# Power_ESP32.net
KiCad netlist of a schematic drawn in Altium Designer
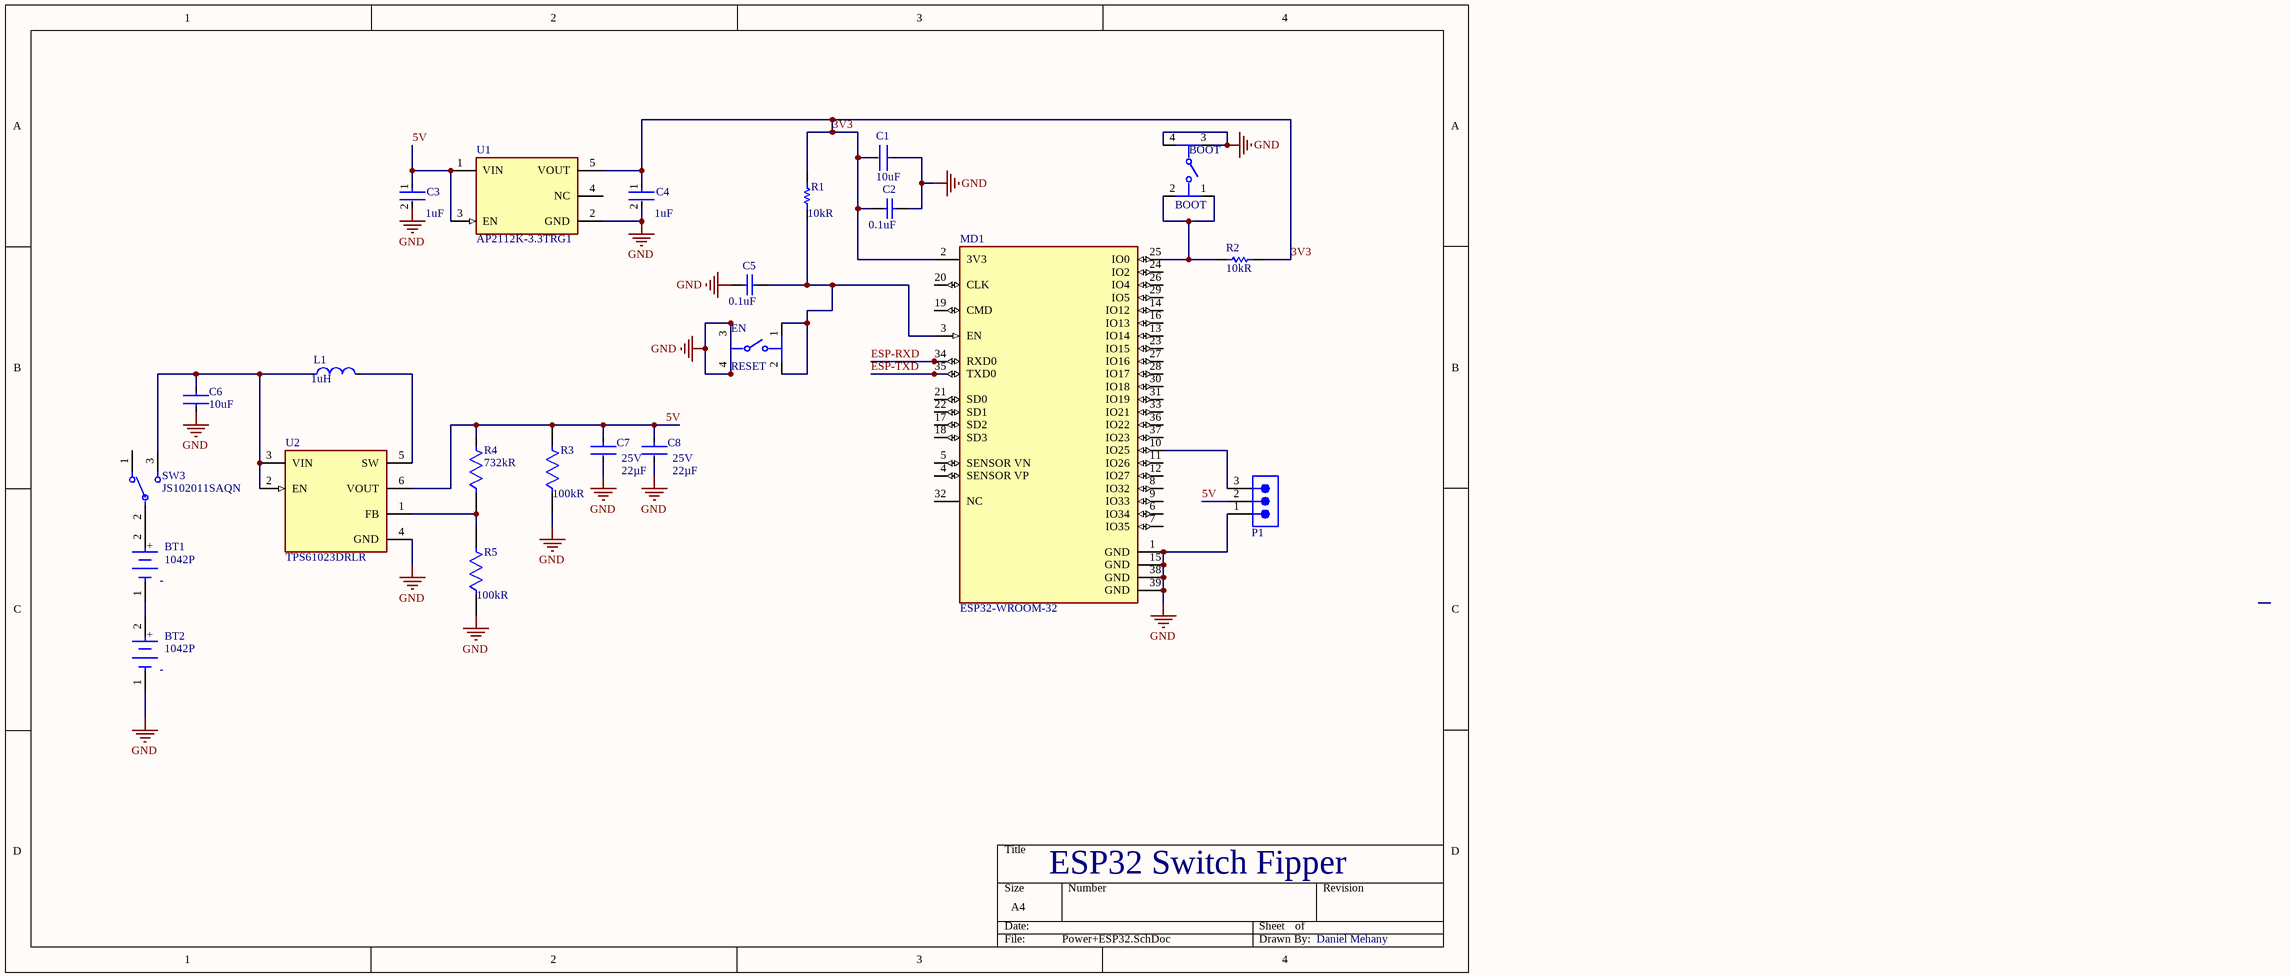
[diagram p0: Power+ESP32.SchDoc]

(export (version "E")
  (design (tool "Eeschema 10.0.6"))
  (components
    (comp (ref "BOOT")
      (value "BOOT")
      (footprint "FP-PTS645SM43SMTR92LFS-MFG")
      (description "SWITCH TACTILE SPST-NO 0.05A 12V")
      (fields (field (name "JLCPCB PART #") "C221880"))
      (libsource (lib "Altium Content Vault") (part "1adf0dd01260c80cf25a44bfd6b99ba"))
    )
    (comp (ref "BT1")
      (value "1042P")
      (footprint "FP-1042P-MFG")
      (description "BATTERY HOLDER 18650 SMD TAB")
      (fields (field (name "JLCPCB PART #") "C6038009"))
      (libsource (lib "Altium Content Vault") (part "60d3b5b901a8747834971d0eb8cf3fd"))
    )
    (comp (ref "BT2")
      (value "1042P")
      (footprint "FP-1042P-MFG")
      (description "BATTERY HOLDER 18650 SMD TAB")
      (fields (field (name "JLCPCB PART #") "C6038009"))
      (libsource (lib "Altium Content Vault") (part "60d3b5b901a8747834971d0eb8cf3fd"))
    )
    (comp (ref "C1")
      (value "10uF")
      (footprint "FP-CL31-IPC_C")
      (description "CAP CER 10UF 50V X5R 1206")
      (fields (field (name "TOLERANCE") "10%") (field (name "MANUFACTURER") "Samsung"))
      (libsource (lib "Altium Content Vault") (part "11868f565c42a9108669ba33697ecf6"))
    )
    (comp (ref "C2")
      (value "CL05B104KO5NNNC")
      (footprint "CAPC1050X55X23ML05T13")
      (description "Chip Capacitor, 100 nF, +/- 10%, 16 V, -55 to 125 degC, 0402 (1005 Metric), RoHS, Tape and Reel")
      (fields
        (field (name "MANUFACTURER") "Samsung Electro-Mechanics")
        (field (name "CAP") "0.1uF")
        (field (name "JLCPCB PART #") "C1525")
      )
      (libsource (lib "Altium Content Vault") (part "CAP-NP-2"))
    )
    (comp (ref "C3")
      (value "CL31B105KBHNNNE")
      (footprint "FP-CL31-IPC_B")
      (description "Cap Ceramic 1uF 50V X7R ±10% SMD 1206 +125°C Embossed T/R")
      (fields
        (field (name "VOLTAGE") "50V")
        (field (name "CAPACITANCE") "1uF")
        (field (name "TOLERANCE") "10%")
      )
      (libsource (lib "Altium Content Vault") (part "b4654b650e69147ec39a6b967a45e02"))
    )
    (comp (ref "C4")
      (value "CL31B105KBHNNNE")
      (footprint "FP-CL31-IPC_B")
      (description "Cap Ceramic 1uF 50V X7R ±10% SMD 1206 +125°C Embossed T/R")
      (fields
        (field (name "VOLTAGE") "50V")
        (field (name "CAPACITANCE") "1uF")
        (field (name "TOLERANCE") "10%")
      )
      (libsource (lib "Altium Content Vault") (part "b4654b650e69147ec39a6b967a45e02"))
    )
    (comp (ref "C5")
      (value "CL05B104KO5NNNC")
      (footprint "CAPC1050X55X23ML05T13")
      (description "Chip Capacitor, 100 nF, +/- 10%, 16 V, -55 to 125 degC, 0402 (1005 Metric), RoHS, Tape and Reel")
      (fields
        (field (name "MANUFACTURER") "Samsung Electro-Mechanics")
        (field (name "CAP") "0.1uF")
        (field (name "JLCPCB PART #") "C1525")
      )
      (libsource (lib "Altium Content Vault") (part "CAP-NP-2"))
    )
    (comp (ref "C6")
      (value "10uF")
      (footprint "FP-CL31-IPC_C")
      (description "CAP CER 10UF 50V X5R 1206")
      (fields (field (name "TOLERANCE") "10%") (field (name "MANUFACTURER") "Samsung"))
      (libsource (lib "Altium Content Vault") (part "11868f565c42a9108669ba33697ecf6"))
    )
    (comp (ref "C7")
      (value "CL31A226KAHNNNE")
      (footprint "CL31H-0_2_MFG")
      (fields (field (name "TOLERANCE") "10%") (field (name "JLCPCB PART #") "C12891"))
      (libsource (lib "Altium Content Vault") (part "fb88589c83559698c54462c48d907c3"))
    )
    (comp (ref "C8")
      (value "CL31A226KAHNNNE")
      (footprint "CL31H-0_2_MFG")
      (fields (field (name "TOLERANCE") "10%") (field (name "JLCPCB PART #") "C12891"))
      (libsource (lib "Altium Content Vault") (part "fb88589c83559698c54462c48d907c3"))
    )
    (comp (ref "EN")
      (value "RESET")
      (footprint "FP-PTS645SM43SMTR92LFS-MFG")
      (description "SWITCH TACTILE SPST-NO 0.05A 12V")
      (fields (field (name "JLCPCB PART #") "C221880"))
      (libsource (lib "Altium Content Vault") (part "1adf0dd01260c80cf25a44bfd6b99ba"))
    )
    (comp (ref "L1")
      (value "1uH")
      (footprint "FP-XAL4020-102MEC-MFG")
      (description "Fixed Inductors 1uH 20% 9.6A 14.60mOhms AEC-Q200")
      (fields
        (field (name "MANUFACTURER") "Coilcraft")
        (field (name "OCTOPART") "https://octopart.com/xal4020-102mec-coilcraft-13142161")
      )
      (libsource (lib "Altium Content Vault") (part "725321dda6339637d4d059423bc1c3c"))
    )
    (comp (ref "MD1")
      (value "ESP32-WROOM-32")
      (footprint "FP-ESP32-WROOM-32-MFG")
      (description "RX TXRX MOD WIFI SURFACE MOUNT")
      (fields (field (name "JLCPCB PART #") "C82899"))
      (libsource (lib "Altium Content Vault") (part "ee866abf0b6c51247b7f5cdebf2f250"))
    )
    (comp (ref "P1")
      (value "TSW-103-07-G-S")
      (footprint "SMTC-TSW-103-07-X-S")
      (description "0.025\" SQ Post Header, Through-hole, Vertical, -55 to 125 degC, 2.54 mm Pitch, 3-Pin, Male, RoHS")
      (fields (field (name "MANUFACTURER") "Samtec") (field (name "JLCPCB PART #") "C3335811"))
      (libsource (lib "Altium Content Vault") (part "SMTC-TSW-103-X-X-S-X"))
    )
    (comp (ref "R1")
      (value "10kR")
      (footprint "RESC2013X60X35NL10T20")
      (description "RES 10kΩ 1% 0.125W 0805")
      (fields (field (name "MANUFACTURER") "Uniroyal") (field (name "MPN") "0805W8F1002T5E"))
      (libsource (lib "Altium Content Vault") (part "RES-2"))
    )
    (comp (ref "R2")
      (value "10kR")
      (footprint "RESC2013X60X35NL10T20")
      (description "RES 10kΩ 1% 0.125W 0805")
      (fields
        (field (name "MANUFACTURER") "Uniroyal")
        (field (name "MANUFACTURER PART NUMBER") "0805W8F1002T5E")
      )
      (libsource (lib "Altium Content Vault") (part "RES-2"))
    )
    (comp (ref "R3")
      (value "100kR")
      (footprint "FP-CRCW0603-HPe3-IPC_C")
      (description "RES Thick Film, 100kΩ, 1%, 0.33W, 100ppm/°C, 0603")
      (fields (field (name "TOLERANCE") "1%") (field (name "MANUFACTURER") "Uniroyal"))
      (libsource (lib "Altium Content Vault") (part "1029c3af85768c4190bb7ad29bc67b5"))
    )
    (comp (ref "R4")
      (value "732kR")
      (footprint "FP-RC0603-0_55-IPC_A")
      (description "RES SMD 732K OHM 1% 1/10W 0603")
      (fields (field (name "TOLERANCE") "1%") (field (name "JLCPCB PART #") "C23239"))
      (libsource (lib "Altium Content Vault") (part "1029c3af85768c4190bb7ad29bc67b5"))
    )
    (comp (ref "R5")
      (value "100kR")
      (footprint "FP-CRCW0603-HPe3-IPC_C")
      (description "RES Thick Film, 100kΩ, 1%, 0.33W, 100ppm/°C, 0603")
      (fields (field (name "TOLERANCE") "1%") (field (name "MANUFACTURER") "Uniroyal"))
      (libsource (lib "Altium Content Vault") (part "1029c3af85768c4190bb7ad29bc67b5"))
    )
    (comp (ref "SW3")
      (value "JS102011SAQN")
      (footprint "FP-JS102011SAQN-MFG")
      (description "SWITCH SLIDE SPDT 300MA 6V")
      (fields (field (name "JLCPCB PART #") "C221660"))
      (libsource (lib "Altium Content Vault") (part "39e195cbbadc85d1df0d7eb6847d379"))
    )
    (comp (ref "U1")
      (value "AP2112K-3.3TRG1")
      (footprint "FP-SOT25-IPC_A")
      (description "IC REG LINEAR 3.3V 600MA SOT25")
      (fields (field (name "JLCPCB PART #") "C51118"))
      (libsource (lib "Altium Content Vault") (part "c8ab751aee5229183125ab046a11caa"))
    )
    (comp (ref "U2")
      (value "TPS61023DRLR")
      (footprint "FP-DRL0006A-MFG")
      (description "FINISH GOODS FOR TPS61023")
      (fields (field (name "JLCPCB PART #") "C919459"))
      (libsource (lib "Altium Content Vault") (part "b28b3e956a4ad07201ce69f9d09f9a8"))
    )
  )
  (nets
    (net (code "1") (name "/3V3") (class "Default")
      (node (ref "C1") (pin "2") (pinfunction "2_2") (pintype "passive"))
      (node (ref "C2") (pin "1") (pinfunction "1_1") (pintype "passive"))
      (node (ref "C4") (pin "1") (pinfunction "1_1") (pintype "passive"))
      (node (ref "MD1") (pin "2") (pinfunction "3V3_2") (pintype "power_in"))
      (node (ref "R1") (pin "2") (pinfunction "2_2") (pintype "passive"))
      (node (ref "R2") (pin "1") (pinfunction "1_1") (pintype "passive"))
      (node (ref "U1") (pin "5") (pinfunction "VOUT_5") (pintype "power_in"))
    )
    (net (code "2") (name "/5V") (class "Default")
      (node (ref "C3") (pin "1") (pinfunction "1_1") (pintype "passive"))
      (node (ref "C7") (pin "1") (pinfunction "1_1") (pintype "passive"))
      (node (ref "C8") (pin "1") (pinfunction "1_1") (pintype "passive"))
      (node (ref "P1") (pin "2") (pinfunction "2_2") (pintype "passive"))
      (node (ref "R3") (pin "2") (pinfunction "2_2") (pintype "passive"))
      (node (ref "R4") (pin "2") (pinfunction "2_2") (pintype "passive"))
      (node (ref "U1") (pin "1") (pinfunction "VIN_1") (pintype "power_in"))
      (node (ref "U1") (pin "3") (pinfunction "EN_3") (pintype "input"))
      (node (ref "U2") (pin "6") (pinfunction "VOUT_6") (pintype "power_in"))
    )
    (net (code "3") (name "/ESP-RXD") (class "Default")
      (node (ref "MD1") (pin "34") (pinfunction "RXD0_34") (pintype "bidirectional"))
    )
    (net (code "4") (name "/ESP-TXD") (class "Default")
      (node (ref "MD1") (pin "35") (pinfunction "TXD0_35") (pintype "bidirectional"))
    )
    (net (code "5") (name "GND") (class "Default")
      (node (ref "BOOT") (pin "3") (pinfunction "3_3") (pintype "passive"))
      (node (ref "BOOT") (pin "4") (pinfunction "4_4") (pintype "passive"))
      (node (ref "BT2") (pin "1") (pinfunction "C_1") (pintype "passive"))
      (node (ref "C1") (pin "1") (pinfunction "1_1") (pintype "passive"))
      (node (ref "C2") (pin "2") (pinfunction "2_2") (pintype "passive"))
      (node (ref "C3") (pin "2") (pinfunction "2_2") (pintype "passive"))
      (node (ref "C4") (pin "2") (pinfunction "2_2") (pintype "passive"))
      (node (ref "C5") (pin "1") (pinfunction "1_1") (pintype "passive"))
      (node (ref "C6") (pin "2") (pinfunction "2_2") (pintype "passive"))
      (node (ref "C7") (pin "2") (pinfunction "2_2") (pintype "passive"))
      (node (ref "C8") (pin "2") (pinfunction "2_2") (pintype "passive"))
      (node (ref "EN") (pin "3") (pinfunction "3_3") (pintype "passive"))
      (node (ref "EN") (pin "4") (pinfunction "4_4") (pintype "passive"))
      (node (ref "MD1") (pin "1") (pinfunction "GND_1") (pintype "power_in"))
      (node (ref "MD1") (pin "15") (pinfunction "GND_15") (pintype "power_in"))
      (node (ref "MD1") (pin "38") (pinfunction "GND_38") (pintype "power_in"))
      (node (ref "MD1") (pin "39") (pinfunction "GND_39") (pintype "power_in"))
      (node (ref "P1") (pin "1") (pinfunction "1_1") (pintype "passive"))
      (node (ref "R3") (pin "1") (pinfunction "1_1") (pintype "passive"))
      (node (ref "R5") (pin "1") (pinfunction "1_1") (pintype "passive"))
      (node (ref "U1") (pin "2") (pinfunction "GND_2") (pintype "power_in"))
      (node (ref "U2") (pin "4") (pinfunction "GND_4") (pintype "power_in"))
    )
    (net (code "6") (name "Net-(BT1-A)") (class "Default")
      (node (ref "BT1") (pin "2") (pinfunction "A_2") (pintype "passive"))
      (node (ref "SW3") (pin "2") (pinfunction "C_2") (pintype "passive"))
    )
    (net (code "7") (name "Net-(BT1-C)") (class "Default")
      (node (ref "BT1") (pin "1") (pinfunction "C_1") (pintype "passive"))
      (node (ref "BT2") (pin "2") (pinfunction "A_2") (pintype "passive"))
    )
    (net (code "8") (name "Net-(MD1-EN)") (class "Default")
      (node (ref "C5") (pin "2") (pinfunction "2_2") (pintype "passive"))
      (node (ref "EN") (pin "1") (pinfunction "1_1") (pintype "passive"))
      (node (ref "EN") (pin "2") (pinfunction "2_2") (pintype "passive"))
      (node (ref "MD1") (pin "3") (pinfunction "EN_3") (pintype "input"))
      (node (ref "R1") (pin "1") (pinfunction "1_1") (pintype "passive"))
    )
    (net (code "9") (name "Net-(MD1-IO0)") (class "Default")
      (node (ref "BOOT") (pin "1") (pinfunction "1_1") (pintype "passive"))
      (node (ref "BOOT") (pin "2") (pinfunction "2_2") (pintype "passive"))
      (node (ref "MD1") (pin "25") (pinfunction "IO0_25") (pintype "bidirectional"))
      (node (ref "R2") (pin "2") (pinfunction "2_2") (pintype "passive"))
    )
    (net (code "10") (name "Net-(MD1-IO25)") (class "Default")
      (node (ref "MD1") (pin "10") (pinfunction "IO25_10") (pintype "bidirectional"))
      (node (ref "P1") (pin "3") (pinfunction "3_3") (pintype "passive"))
    )
    (net (code "11") (name "Net-(U2-EN)") (class "Default")
      (node (ref "C6") (pin "1") (pinfunction "1_1") (pintype "passive"))
      (node (ref "L1") (pin "1") (pinfunction "1_1") (pintype "passive"))
      (node (ref "SW3") (pin "3") (pinfunction "3_3") (pintype "passive"))
      (node (ref "U2") (pin "2") (pinfunction "EN_2") (pintype "input"))
      (node (ref "U2") (pin "3") (pinfunction "VIN_3") (pintype "power_in"))
    )
    (net (code "12") (name "Net-(U2-FB)") (class "Default")
      (node (ref "R4") (pin "1") (pinfunction "1_1") (pintype "passive"))
      (node (ref "R5") (pin "2") (pinfunction "2_2") (pintype "passive"))
      (node (ref "U2") (pin "1") (pinfunction "FB_1") (pintype "passive"))
    )
    (net (code "13") (name "Net-(U2-SW)") (class "Default")
      (node (ref "L1") (pin "2") (pinfunction "2_2") (pintype "passive"))
      (node (ref "U2") (pin "5") (pinfunction "SW_5") (pintype "passive"))
    )
    (net (code "14") (name "unconnected-(MD1-CLK-Pad20)") (class "Default")
      (node (ref "MD1") (pin "20") (pinfunction "CLK_20") (pintype "bidirectional"))
    )
    (net (code "15") (name "unconnected-(MD1-CMD-Pad19)") (class "Default")
      (node (ref "MD1") (pin "19") (pinfunction "CMD_19") (pintype "bidirectional"))
    )
    (net (code "16") (name "unconnected-(MD1-IO2-Pad24)") (class "Default")
      (node (ref "MD1") (pin "24") (pinfunction "IO2_24") (pintype "bidirectional"))
    )
    (net (code "17") (name "unconnected-(MD1-IO4-Pad26)") (class "Default")
      (node (ref "MD1") (pin "26") (pinfunction "IO4_26") (pintype "bidirectional"))
    )
    (net (code "18") (name "unconnected-(MD1-IO5-Pad29)") (class "Default")
      (node (ref "MD1") (pin "29") (pinfunction "IO5_29") (pintype "bidirectional"))
    )
    (net (code "19") (name "unconnected-(MD1-IO12-Pad14)") (class "Default")
      (node (ref "MD1") (pin "14") (pinfunction "IO12_14") (pintype "bidirectional"))
    )
    (net (code "20") (name "unconnected-(MD1-IO13-Pad16)") (class "Default")
      (node (ref "MD1") (pin "16") (pinfunction "IO13_16") (pintype "bidirectional"))
    )
    (net (code "21") (name "unconnected-(MD1-IO14-Pad13)") (class "Default")
      (node (ref "MD1") (pin "13") (pinfunction "IO14_13") (pintype "bidirectional"))
    )
    (net (code "22") (name "unconnected-(MD1-IO15-Pad23)") (class "Default")
      (node (ref "MD1") (pin "23") (pinfunction "IO15_23") (pintype "bidirectional"))
    )
    (net (code "23") (name "unconnected-(MD1-IO16-Pad27)") (class "Default")
      (node (ref "MD1") (pin "27") (pinfunction "IO16_27") (pintype "bidirectional"))
    )
    (net (code "24") (name "unconnected-(MD1-IO17-Pad28)") (class "Default")
      (node (ref "MD1") (pin "28") (pinfunction "IO17_28") (pintype "bidirectional"))
    )
    (net (code "25") (name "unconnected-(MD1-IO18-Pad30)") (class "Default")
      (node (ref "MD1") (pin "30") (pinfunction "IO18_30") (pintype "bidirectional"))
    )
    (net (code "26") (name "unconnected-(MD1-IO19-Pad31)") (class "Default")
      (node (ref "MD1") (pin "31") (pinfunction "IO19_31") (pintype "bidirectional"))
    )
    (net (code "27") (name "unconnected-(MD1-IO21-Pad33)") (class "Default")
      (node (ref "MD1") (pin "33") (pinfunction "IO21_33") (pintype "bidirectional"))
    )
    (net (code "28") (name "unconnected-(MD1-IO22-Pad36)") (class "Default")
      (node (ref "MD1") (pin "36") (pinfunction "IO22_36") (pintype "bidirectional"))
    )
    (net (code "29") (name "unconnected-(MD1-IO23-Pad37)") (class "Default")
      (node (ref "MD1") (pin "37") (pinfunction "IO23_37") (pintype "bidirectional"))
    )
    (net (code "30") (name "unconnected-(MD1-IO26-Pad11)") (class "Default")
      (node (ref "MD1") (pin "11") (pinfunction "IO26_11") (pintype "bidirectional"))
    )
    (net (code "31") (name "unconnected-(MD1-IO27-Pad12)") (class "Default")
      (node (ref "MD1") (pin "12") (pinfunction "IO27_12") (pintype "bidirectional"))
    )
    (net (code "32") (name "unconnected-(MD1-IO32-Pad8)") (class "Default")
      (node (ref "MD1") (pin "8") (pinfunction "IO32_8") (pintype "bidirectional"))
    )
    (net (code "33") (name "unconnected-(MD1-IO33-Pad9)") (class "Default")
      (node (ref "MD1") (pin "9") (pinfunction "IO33_9") (pintype "bidirectional"))
    )
    (net (code "34") (name "unconnected-(MD1-IO34-Pad6)") (class "Default")
      (node (ref "MD1") (pin "6") (pinfunction "IO34_6") (pintype "bidirectional"))
    )
    (net (code "35") (name "unconnected-(MD1-IO35-Pad7)") (class "Default")
      (node (ref "MD1") (pin "7") (pinfunction "IO35_7") (pintype "bidirectional"))
    )
    (net (code "36") (name "unconnected-(MD1-NC-Pad32)") (class "Default")
      (node (ref "MD1") (pin "32") (pinfunction "NC_32") (pintype "passive"))
    )
    (net (code "37") (name "unconnected-(MD1-SD0-Pad21)") (class "Default")
      (node (ref "MD1") (pin "21") (pinfunction "SD0_21") (pintype "bidirectional"))
    )
    (net (code "38") (name "unconnected-(MD1-SD1-Pad22)") (class "Default")
      (node (ref "MD1") (pin "22") (pinfunction "SD1_22") (pintype "bidirectional"))
    )
    (net (code "39") (name "unconnected-(MD1-SD2-Pad17)") (class "Default")
      (node (ref "MD1") (pin "17") (pinfunction "SD2_17") (pintype "bidirectional"))
    )
    (net (code "40") (name "unconnected-(MD1-SD3-Pad18)") (class "Default")
      (node (ref "MD1") (pin "18") (pinfunction "SD3_18") (pintype "bidirectional"))
    )
    (net (code "41") (name "unconnected-(MD1-SENSOR_VN-Pad5)") (class "Default")
      (node (ref "MD1") (pin "5") (pinfunction "SENSOR_VN_5") (pintype "bidirectional"))
    )
    (net (code "42") (name "unconnected-(MD1-SENSOR_VP-Pad4)") (class "Default")
      (node (ref "MD1") (pin "4") (pinfunction "SENSOR_VP_4") (pintype "bidirectional"))
    )
    (net (code "43") (name "unconnected-(SW3-Pad1)") (class "Default")
      (node (ref "SW3") (pin "1") (pinfunction "1_1") (pintype "passive"))
    )
    (net (code "44") (name "unconnected-(U1-NC-Pad4)") (class "Default")
      (node (ref "U1") (pin "4") (pinfunction "NC_4") (pintype "passive"))
    )
  )
)
